# IMU_Sch.net
KiCad netlist of a schematic drawn in Altium Designer
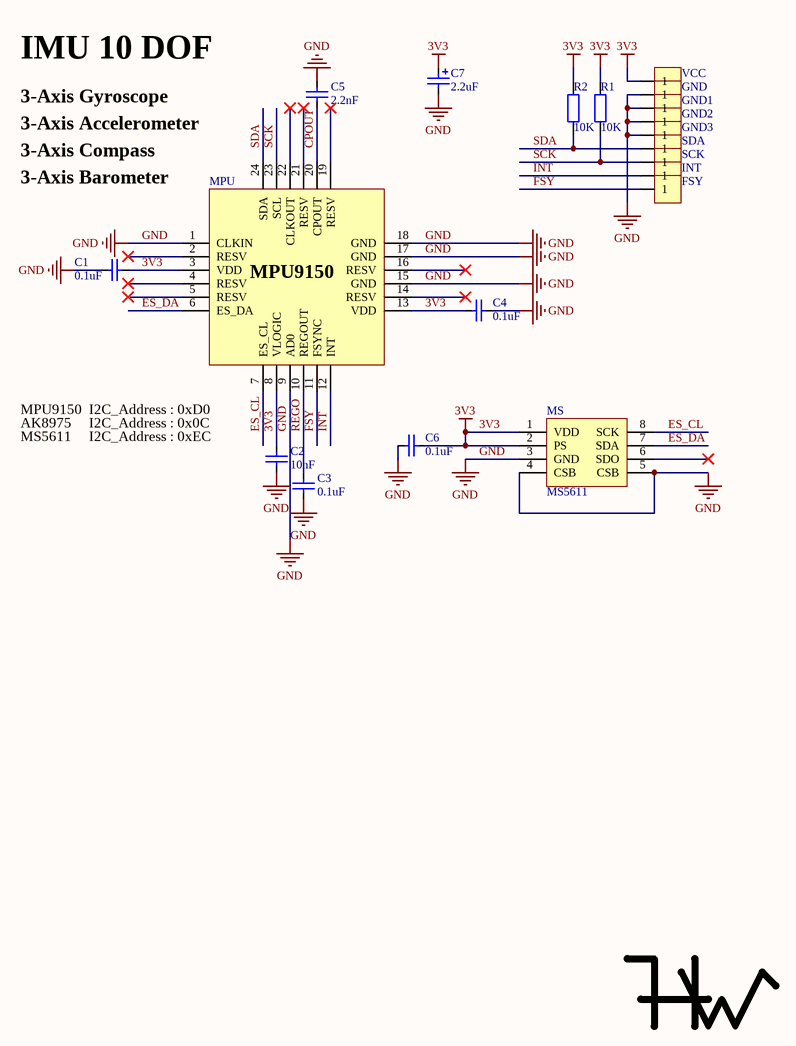
[diagram p0: IMU_Sch.SchDoc]

(export (version "E")
  (design (tool "Eeschema 10.0.6"))
  (components
    (comp (ref "C1")
      (value "0.1uF")
      (footprint "PCB_Passive:CAP_0603")
      (description "Capacitor")
      (fields (field (name "Comment") "Cap_0603"))
      (libsource (lib "SCH_Passive") (part "Cap_0603"))
    )
    (comp (ref "C2")
      (value "10nF")
      (footprint "PCB_Passive:CAP_0603")
      (description "Capacitor")
      (fields (field (name "Comment") "Cap_0603"))
      (libsource (lib "SCH_Passive") (part "Cap_0603"))
    )
    (comp (ref "C3")
      (value "0.1uF")
      (footprint "PCB_Passive:CAP_0603")
      (description "Capacitor")
      (fields (field (name "Comment") "Cap_0603"))
      (libsource (lib "SCH_Passive") (part "Cap_0603"))
    )
    (comp (ref "C4")
      (value "0.1uF")
      (footprint "PCB_Passive:CAP_0603")
      (description "Capacitor")
      (fields (field (name "Comment") "Cap_0603"))
      (libsource (lib "SCH_Passive") (part "Cap_0603"))
    )
    (comp (ref "C5")
      (value "2.2nF")
      (footprint "PCB_Passive:CAP_0603")
      (description "Capacitor")
      (fields (field (name "Comment") "Cap_0603"))
      (libsource (lib "SCH_Passive") (part "Cap_0603"))
    )
    (comp (ref "C6")
      (value "0.1uF")
      (footprint "PCB_Passive:CAP_0603")
      (description "Capacitor")
      (fields (field (name "Comment") "Cap_0603"))
      (libsource (lib "SCH_Passive") (part "Cap_0603"))
    )
    (comp (ref "C7")
      (value "2.2uF")
      (footprint "PCB_Passive:CAP_TAN_P0805")
      (description "Capacitor")
      (fields (field (name "Comment") "Cap_Tan_0805"))
      (libsource (lib "SCH_Passive") (part "Cap_Tan_0805"))
    )
    (comp (ref "FSY")
      (value "Pad1X1_1.27")
      (footprint "PCB_Connector:Pad1X1_1.27")
      (description "Header")
      (libsource (lib "SCH_Connector") (part "Pad1X1_1.27"))
    )
    (comp (ref "GND")
      (value "Pad1X1_1.27")
      (footprint "PCB_Connector:Pad1X1_1.27")
      (description "Header")
      (libsource (lib "SCH_Connector") (part "Pad1X1_1.27"))
    )
    (comp (ref "GND1")
      (value "Pad1X1_1.27")
      (footprint "PCB_Connector:Pad1X1_1.27")
      (description "Header")
      (libsource (lib "SCH_Connector") (part "Pad1X1_1.27"))
    )
    (comp (ref "GND2")
      (value "Pad1X1_1.27")
      (footprint "PCB_Connector:Pad1X1_1.27")
      (description "Header")
      (libsource (lib "SCH_Connector") (part "Pad1X1_1.27"))
    )
    (comp (ref "GND3")
      (value "Pad1X1_1.27")
      (footprint "PCB_Connector:Pad1X1_1.27")
      (description "Header")
      (libsource (lib "SCH_Connector") (part "Pad1X1_1.27"))
    )
    (comp (ref "INT")
      (value "Pad1X1_1.27")
      (footprint "PCB_Connector:Pad1X1_1.27")
      (description "Header")
      (libsource (lib "SCH_Connector") (part "Pad1X1_1.27"))
    )
    (comp (ref "Mark") (value "Mark") (footprint "PCB_Mark:HW_Mark") (libsource (lib "SCH_Mark") (part "HW")))
    (comp (ref "MPU")
      (value "MPU9150")
      (footprint "PCB_IC:MPU9150")
      (description "Sensor")
      (libsource (lib "SCH_IC") (part "MPU9150"))
    )
    (comp (ref "MS")
      (value "MS5611")
      (footprint "MS5611")
      (description "Sensor")
      (libsource (lib "SCH_IC") (part "MS5611"))
    )
    (comp (ref "R1")
      (value "10K")
      (footprint "PCB_Passive:RES_0603")
      (description "Resistor")
      (fields (field (name "Comment") "Res_0603"))
      (libsource (lib "SCH_Passive") (part "Res_0603"))
    )
    (comp (ref "R2")
      (value "10K")
      (footprint "PCB_Passive:RES_0603")
      (description "Resistor")
      (fields (field (name "Comment") "Res_0603"))
      (libsource (lib "SCH_Passive") (part "Res_0603"))
    )
    (comp (ref "SCK")
      (value "Pad1X1_1.27")
      (footprint "PCB_Connector:Pad1X1_1.27")
      (description "Header")
      (libsource (lib "SCH_Connector") (part "Pad1X1_1.27"))
    )
    (comp (ref "SDA")
      (value "Pad1X1_1.27")
      (footprint "PCB_Connector:Pad1X1_1.27")
      (description "Header")
      (libsource (lib "SCH_Connector") (part "Pad1X1_1.27"))
    )
    (comp (ref "VCC")
      (value "Pad1X1_1.27")
      (footprint "PCB_Connector:Pad1X1_1.27")
      (description "Header")
      (libsource (lib "SCH_Connector") (part "Pad1X1_1.27"))
    )
  )
  (nets
    (net (code "1") (name "/CPOUT") (class "Default")
      (node (ref "C5") (pin "1") (pinfunction "1_1") (pintype "passive"))
      (node (ref "MPU") (pin "20") (pinfunction "CPOUT_20") (pintype "passive"))
    )
    (net (code "2") (name "/ES_CL") (class "Default")
      (node (ref "MPU") (pin "7") (pinfunction "ES_CL_7") (pintype "passive"))
      (node (ref "MS") (pin "8") (pinfunction "SCK_8") (pintype "passive"))
    )
    (net (code "3") (name "/ES_DA") (class "Default")
      (node (ref "MPU") (pin "6") (pinfunction "ES_DA_6") (pintype "passive"))
      (node (ref "MS") (pin "7") (pinfunction "SDA_7") (pintype "passive"))
    )
    (net (code "4") (name "/FSY") (class "Default")
      (node (ref "FSY") (pin "1") (pinfunction "1_1") (pintype "passive"))
      (node (ref "MPU") (pin "11") (pinfunction "FSYNC_11") (pintype "passive"))
    )
    (net (code "5") (name "/INT") (class "Default")
      (node (ref "INT") (pin "1") (pinfunction "1_1") (pintype "passive"))
      (node (ref "MPU") (pin "12") (pinfunction "INT_12") (pintype "passive"))
    )
    (net (code "6") (name "/REGO") (class "Default")
      (node (ref "C3") (pin "2") (pinfunction "2_2") (pintype "passive"))
      (node (ref "MPU") (pin "10") (pinfunction "REGOUT_10") (pintype "passive"))
    )
    (net (code "7") (name "/SCK") (class "Default")
      (node (ref "MPU") (pin "23") (pinfunction "SCL_23") (pintype "passive"))
      (node (ref "R1") (pin "2") (pinfunction "2_2") (pintype "passive"))
      (node (ref "SCK") (pin "1") (pinfunction "1_1") (pintype "passive"))
    )
    (net (code "8") (name "/SDA") (class "Default")
      (node (ref "MPU") (pin "24") (pinfunction "SDA_24") (pintype "passive"))
      (node (ref "R2") (pin "2") (pinfunction "2_2") (pintype "passive"))
      (node (ref "SDA") (pin "1") (pinfunction "1_1") (pintype "passive"))
    )
    (net (code "9") (name "3V3") (class "Default")
      (node (ref "C1") (pin "2") (pinfunction "2_2") (pintype "passive"))
      (node (ref "C2") (pin "2") (pinfunction "2_2") (pintype "passive"))
      (node (ref "C4") (pin "2") (pinfunction "2_2") (pintype "passive"))
      (node (ref "C6") (pin "1") (pinfunction "1_1") (pintype "passive"))
      (node (ref "C7") (pin "1") (pinfunction "1_1") (pintype "passive"))
      (node (ref "MPU") (pin "13") (pinfunction "VDD_13") (pintype "passive"))
      (node (ref "MPU") (pin "3") (pinfunction "VDD_3") (pintype "passive"))
      (node (ref "MPU") (pin "8") (pinfunction "VLOGIC_8") (pintype "passive"))
      (node (ref "MS") (pin "1") (pinfunction "VDD_1") (pintype "passive"))
      (node (ref "MS") (pin "2") (pinfunction "PS_2") (pintype "passive"))
      (node (ref "R1") (pin "1") (pinfunction "1_1") (pintype "passive"))
      (node (ref "R2") (pin "1") (pinfunction "1_1") (pintype "passive"))
      (node (ref "VCC") (pin "1") (pinfunction "1_1") (pintype "passive"))
    )
    (net (code "10") (name "GND") (class "Default")
      (node (ref "C1") (pin "1") (pinfunction "1_1") (pintype "passive"))
      (node (ref "C2") (pin "1") (pinfunction "1_1") (pintype "passive"))
      (node (ref "C3") (pin "1") (pinfunction "1_1") (pintype "passive"))
      (node (ref "C4") (pin "1") (pinfunction "1_1") (pintype "passive"))
      (node (ref "C5") (pin "2") (pinfunction "2_2") (pintype "passive"))
      (node (ref "C6") (pin "2") (pinfunction "2_2") (pintype "passive"))
      (node (ref "C7") (pin "2") (pinfunction "2_2") (pintype "passive"))
      (node (ref "GND") (pin "1") (pinfunction "1_1") (pintype "passive"))
      (node (ref "GND1") (pin "1") (pinfunction "1_1") (pintype "passive"))
      (node (ref "GND2") (pin "1") (pinfunction "1_1") (pintype "passive"))
      (node (ref "GND3") (pin "1") (pinfunction "1_1") (pintype "passive"))
      (node (ref "MPU") (pin "1") (pinfunction "CLKIN_1") (pintype "passive"))
      (node (ref "MPU") (pin "15") (pinfunction "GND_15") (pintype "passive"))
      (node (ref "MPU") (pin "17") (pinfunction "GND_17") (pintype "passive"))
      (node (ref "MPU") (pin "18") (pinfunction "GND_18") (pintype "passive"))
      (node (ref "MPU") (pin "9") (pinfunction "AD0_9") (pintype "passive"))
      (node (ref "MS") (pin "3") (pinfunction "GND_3") (pintype "passive"))
      (node (ref "MS") (pin "4") (pinfunction "CSB_4") (pintype "passive"))
      (node (ref "MS") (pin "5") (pinfunction "CSB_5") (pintype "passive"))
    )
    (net (code "11") (name "unconnected-(MPU-CLKOUT-Pad22)") (class "Default")
      (node (ref "MPU") (pin "22") (pinfunction "CLKOUT_22") (pintype "passive+no_connect"))
    )
    (net (code "12") (name "unconnected-(MPU-RESV-Pad2)") (class "Default")
      (node (ref "MPU") (pin "2") (pinfunction "RESV_2") (pintype "passive+no_connect"))
    )
    (net (code "13") (name "unconnected-(MPU-RESV-Pad4)") (class "Default")
      (node (ref "MPU") (pin "4") (pinfunction "RESV_4") (pintype "passive+no_connect"))
    )
    (net (code "14") (name "unconnected-(MPU-RESV-Pad5)") (class "Default")
      (node (ref "MPU") (pin "5") (pinfunction "RESV_5") (pintype "passive+no_connect"))
    )
    (net (code "15") (name "unconnected-(MPU-RESV-Pad14)") (class "Default")
      (node (ref "MPU") (pin "14") (pinfunction "RESV_14") (pintype "passive+no_connect"))
    )
    (net (code "16") (name "unconnected-(MPU-RESV-Pad16)") (class "Default")
      (node (ref "MPU") (pin "16") (pinfunction "RESV_16") (pintype "passive+no_connect"))
    )
    (net (code "17") (name "unconnected-(MPU-RESV-Pad19)") (class "Default")
      (node (ref "MPU") (pin "19") (pinfunction "RESV_19") (pintype "passive+no_connect"))
    )
    (net (code "18") (name "unconnected-(MPU-RESV-Pad21)") (class "Default")
      (node (ref "MPU") (pin "21") (pinfunction "RESV_21") (pintype "passive+no_connect"))
    )
    (net (code "19") (name "unconnected-(MS-SDO-Pad6)") (class "Default")
      (node (ref "MS") (pin "6") (pinfunction "SDO_6") (pintype "passive+no_connect"))
    )
  )
)
